# RP2040_Evaluation_Design.net
KiCad netlist of a schematic drawn in Altium Designer
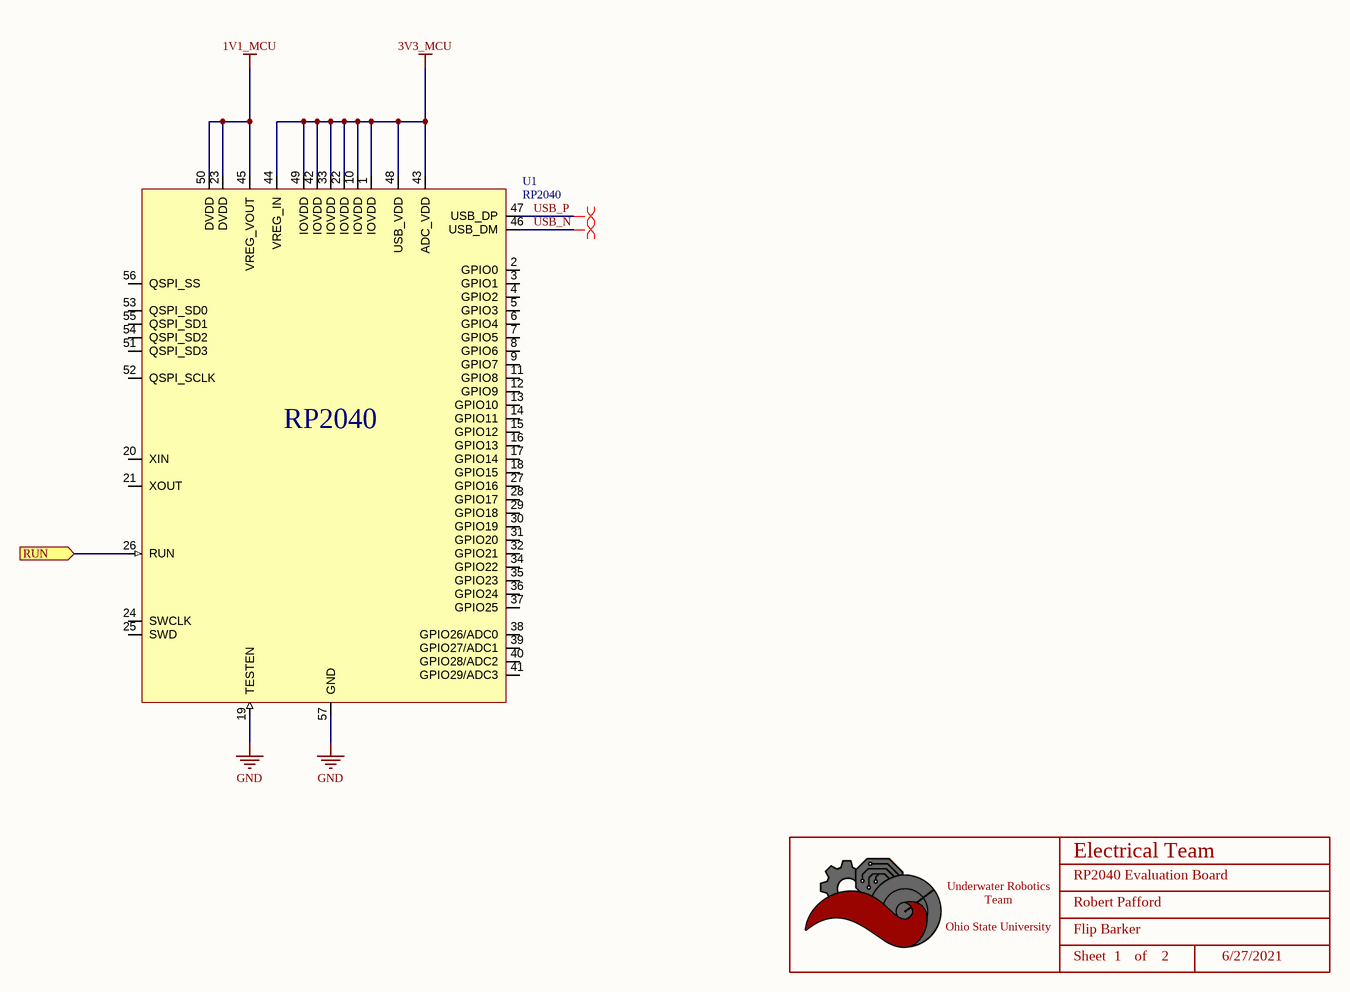
[diagram p0: RP2040_Evaluation_Design.SchDoc]

(export (version "E")
  (design (tool "Eeschema 10.0.6"))
  (components
    (comp (ref "*")
      (value "Title_Block")
      (description "UWRT Schematic Title Block Template\r\n\r\nCreated June 2021, Dylan Trainor")
      (libsource (lib "Sch_Templates") (part "Title_Block"))
    )
    (comp (ref "U1")
      (value "RP2040")
      (footprint "QFN-56 RP2040")
      (description "Raspberry Pi RP2040")
      (libsource (lib "UWRT") (part "RP2040"))
    )
  )
  (nets
    (net (code "1") (name "/RUN") (class "Default")
      (node (ref "U1") (pin "26") (pinfunction "RUN_26") (pintype "input"))
    )
    (net (code "2") (name "/USB_N") (class "Default")
      (node (ref "U1") (pin "46") (pinfunction "USB_DM_46") (pintype "bidirectional"))
    )
    (net (code "3") (name "/USB_P") (class "Default")
      (node (ref "U1") (pin "47") (pinfunction "USB_DP_47") (pintype "bidirectional"))
    )
    (net (code "4") (name "1V1_MCU") (class "Default")
      (node (ref "U1") (pin "23") (pinfunction "DVDD_23") (pintype "power_in"))
      (node (ref "U1") (pin "45") (pinfunction "VREG_VOUT_45") (pintype "power_in"))
      (node (ref "U1") (pin "50") (pinfunction "DVDD_50") (pintype "power_in"))
    )
    (net (code "5") (name "3V3_MCU") (class "Default")
      (node (ref "U1") (pin "1") (pinfunction "IOVDD_1") (pintype "power_in"))
      (node (ref "U1") (pin "10") (pinfunction "IOVDD_10") (pintype "power_in"))
      (node (ref "U1") (pin "22") (pinfunction "IOVDD_22") (pintype "power_in"))
      (node (ref "U1") (pin "33") (pinfunction "IOVDD_33") (pintype "power_in"))
      (node (ref "U1") (pin "42") (pinfunction "IOVDD_42") (pintype "power_in"))
      (node (ref "U1") (pin "43") (pinfunction "ADC_VDD_43") (pintype "power_in"))
      (node (ref "U1") (pin "44") (pinfunction "VREG_IN_44") (pintype "power_in"))
      (node (ref "U1") (pin "48") (pinfunction "USB_VDD_48") (pintype "power_in"))
      (node (ref "U1") (pin "49") (pinfunction "IOVDD_49") (pintype "power_in"))
    )
    (net (code "6") (name "GND") (class "Default")
      (node (ref "U1") (pin "19") (pinfunction "TESTEN_19") (pintype "input"))
      (node (ref "U1") (pin "57") (pinfunction "GND_57") (pintype "power_in"))
    )
    (net (code "7") (name "unconnected-(U1-GPIO0-Pad2)") (class "Default")
      (node (ref "U1") (pin "2") (pinfunction "GPIO0_2") (pintype "bidirectional"))
    )
    (net (code "8") (name "unconnected-(U1-GPIO1-Pad3)") (class "Default")
      (node (ref "U1") (pin "3") (pinfunction "GPIO1_3") (pintype "bidirectional"))
    )
    (net (code "9") (name "unconnected-(U1-GPIO2-Pad4)") (class "Default")
      (node (ref "U1") (pin "4") (pinfunction "GPIO2_4") (pintype "bidirectional"))
    )
    (net (code "10") (name "unconnected-(U1-GPIO3-Pad5)") (class "Default")
      (node (ref "U1") (pin "5") (pinfunction "GPIO3_5") (pintype "bidirectional"))
    )
    (net (code "11") (name "unconnected-(U1-GPIO4-Pad6)") (class "Default")
      (node (ref "U1") (pin "6") (pinfunction "GPIO4_6") (pintype "bidirectional"))
    )
    (net (code "12") (name "unconnected-(U1-GPIO5-Pad7)") (class "Default")
      (node (ref "U1") (pin "7") (pinfunction "GPIO5_7") (pintype "bidirectional"))
    )
    (net (code "13") (name "unconnected-(U1-GPIO6-Pad8)") (class "Default")
      (node (ref "U1") (pin "8") (pinfunction "GPIO6_8") (pintype "bidirectional"))
    )
    (net (code "14") (name "unconnected-(U1-GPIO7-Pad9)") (class "Default")
      (node (ref "U1") (pin "9") (pinfunction "GPIO7_9") (pintype "bidirectional"))
    )
    (net (code "15") (name "unconnected-(U1-GPIO8-Pad11)") (class "Default")
      (node (ref "U1") (pin "11") (pinfunction "GPIO8_11") (pintype "bidirectional"))
    )
    (net (code "16") (name "unconnected-(U1-GPIO9-Pad12)") (class "Default")
      (node (ref "U1") (pin "12") (pinfunction "GPIO9_12") (pintype "bidirectional"))
    )
    (net (code "17") (name "unconnected-(U1-GPIO10-Pad13)") (class "Default")
      (node (ref "U1") (pin "13") (pinfunction "GPIO10_13") (pintype "bidirectional"))
    )
    (net (code "18") (name "unconnected-(U1-GPIO11-Pad14)") (class "Default")
      (node (ref "U1") (pin "14") (pinfunction "GPIO11_14") (pintype "bidirectional"))
    )
    (net (code "19") (name "unconnected-(U1-GPIO12-Pad15)") (class "Default")
      (node (ref "U1") (pin "15") (pinfunction "GPIO12_15") (pintype "bidirectional"))
    )
    (net (code "20") (name "unconnected-(U1-GPIO13-Pad16)") (class "Default")
      (node (ref "U1") (pin "16") (pinfunction "GPIO13_16") (pintype "bidirectional"))
    )
    (net (code "21") (name "unconnected-(U1-GPIO14-Pad17)") (class "Default")
      (node (ref "U1") (pin "17") (pinfunction "GPIO14_17") (pintype "bidirectional"))
    )
    (net (code "22") (name "unconnected-(U1-GPIO15-Pad18)") (class "Default")
      (node (ref "U1") (pin "18") (pinfunction "GPIO15_18") (pintype "bidirectional"))
    )
    (net (code "23") (name "unconnected-(U1-GPIO16-Pad27)") (class "Default")
      (node (ref "U1") (pin "27") (pinfunction "GPIO16_27") (pintype "bidirectional"))
    )
    (net (code "24") (name "unconnected-(U1-GPIO17-Pad28)") (class "Default")
      (node (ref "U1") (pin "28") (pinfunction "GPIO17_28") (pintype "bidirectional"))
    )
    (net (code "25") (name "unconnected-(U1-GPIO18-Pad29)") (class "Default")
      (node (ref "U1") (pin "29") (pinfunction "GPIO18_29") (pintype "bidirectional"))
    )
    (net (code "26") (name "unconnected-(U1-GPIO19-Pad30)") (class "Default")
      (node (ref "U1") (pin "30") (pinfunction "GPIO19_30") (pintype "bidirectional"))
    )
    (net (code "27") (name "unconnected-(U1-GPIO20-Pad31)") (class "Default")
      (node (ref "U1") (pin "31") (pinfunction "GPIO20_31") (pintype "bidirectional"))
    )
    (net (code "28") (name "unconnected-(U1-GPIO21-Pad32)") (class "Default")
      (node (ref "U1") (pin "32") (pinfunction "GPIO21_32") (pintype "bidirectional"))
    )
    (net (code "29") (name "unconnected-(U1-GPIO22-Pad34)") (class "Default")
      (node (ref "U1") (pin "34") (pinfunction "GPIO22_34") (pintype "bidirectional"))
    )
    (net (code "30") (name "unconnected-(U1-GPIO23-Pad35)") (class "Default")
      (node (ref "U1") (pin "35") (pinfunction "GPIO23_35") (pintype "bidirectional"))
    )
    (net (code "31") (name "unconnected-(U1-GPIO24-Pad36)") (class "Default")
      (node (ref "U1") (pin "36") (pinfunction "GPIO24_36") (pintype "bidirectional"))
    )
    (net (code "32") (name "unconnected-(U1-GPIO25-Pad37)") (class "Default")
      (node (ref "U1") (pin "37") (pinfunction "GPIO25_37") (pintype "bidirectional"))
    )
    (net (code "33") (name "unconnected-(U1-GPIO26{slash}ADC0-Pad38)") (class "Default")
      (node (ref "U1") (pin "38") (pinfunction "GPIO26/ADC0_38") (pintype "bidirectional"))
    )
    (net (code "34") (name "unconnected-(U1-GPIO27{slash}ADC1-Pad39)") (class "Default")
      (node (ref "U1") (pin "39") (pinfunction "GPIO27/ADC1_39") (pintype "bidirectional"))
    )
    (net (code "35") (name "unconnected-(U1-GPIO28{slash}ADC2-Pad40)") (class "Default")
      (node (ref "U1") (pin "40") (pinfunction "GPIO28/ADC2_40") (pintype "bidirectional"))
    )
    (net (code "36") (name "unconnected-(U1-GPIO29{slash}ADC3-Pad41)") (class "Default")
      (node (ref "U1") (pin "41") (pinfunction "GPIO29/ADC3_41") (pintype "bidirectional"))
    )
    (net (code "37") (name "unconnected-(U1-QSPI_SCLK-Pad52)") (class "Default")
      (node (ref "U1") (pin "52") (pinfunction "QSPI_SCLK_52") (pintype "bidirectional"))
    )
    (net (code "38") (name "unconnected-(U1-QSPI_SD0-Pad53)") (class "Default")
      (node (ref "U1") (pin "53") (pinfunction "QSPI_SD0_53") (pintype "bidirectional"))
    )
    (net (code "39") (name "unconnected-(U1-QSPI_SD1-Pad55)") (class "Default")
      (node (ref "U1") (pin "55") (pinfunction "QSPI_SD1_55") (pintype "bidirectional"))
    )
    (net (code "40") (name "unconnected-(U1-QSPI_SD2-Pad54)") (class "Default")
      (node (ref "U1") (pin "54") (pinfunction "QSPI_SD2_54") (pintype "bidirectional"))
    )
    (net (code "41") (name "unconnected-(U1-QSPI_SD3-Pad51)") (class "Default")
      (node (ref "U1") (pin "51") (pinfunction "QSPI_SD3_51") (pintype "bidirectional"))
    )
    (net (code "42") (name "unconnected-(U1-QSPI_SS-Pad56)") (class "Default")
      (node (ref "U1") (pin "56") (pinfunction "QSPI_SS_56") (pintype "bidirectional"))
    )
    (net (code "43") (name "unconnected-(U1-SWCLK-Pad24)") (class "Default")
      (node (ref "U1") (pin "24") (pinfunction "SWCLK_24") (pintype "bidirectional"))
    )
    (net (code "44") (name "unconnected-(U1-SWD-Pad25)") (class "Default")
      (node (ref "U1") (pin "25") (pinfunction "SWD_25") (pintype "bidirectional"))
    )
    (net (code "45") (name "unconnected-(U1-XIN-Pad20)") (class "Default")
      (node (ref "U1") (pin "20") (pinfunction "XIN_20") (pintype "passive"))
    )
    (net (code "46") (name "unconnected-(U1-XOUT-Pad21)") (class "Default")
      (node (ref "U1") (pin "21") (pinfunction "XOUT_21") (pintype "passive"))
    )
  )
)
